# tempo_counter.net
KiCad netlist of a schematic drawn in EAGLE
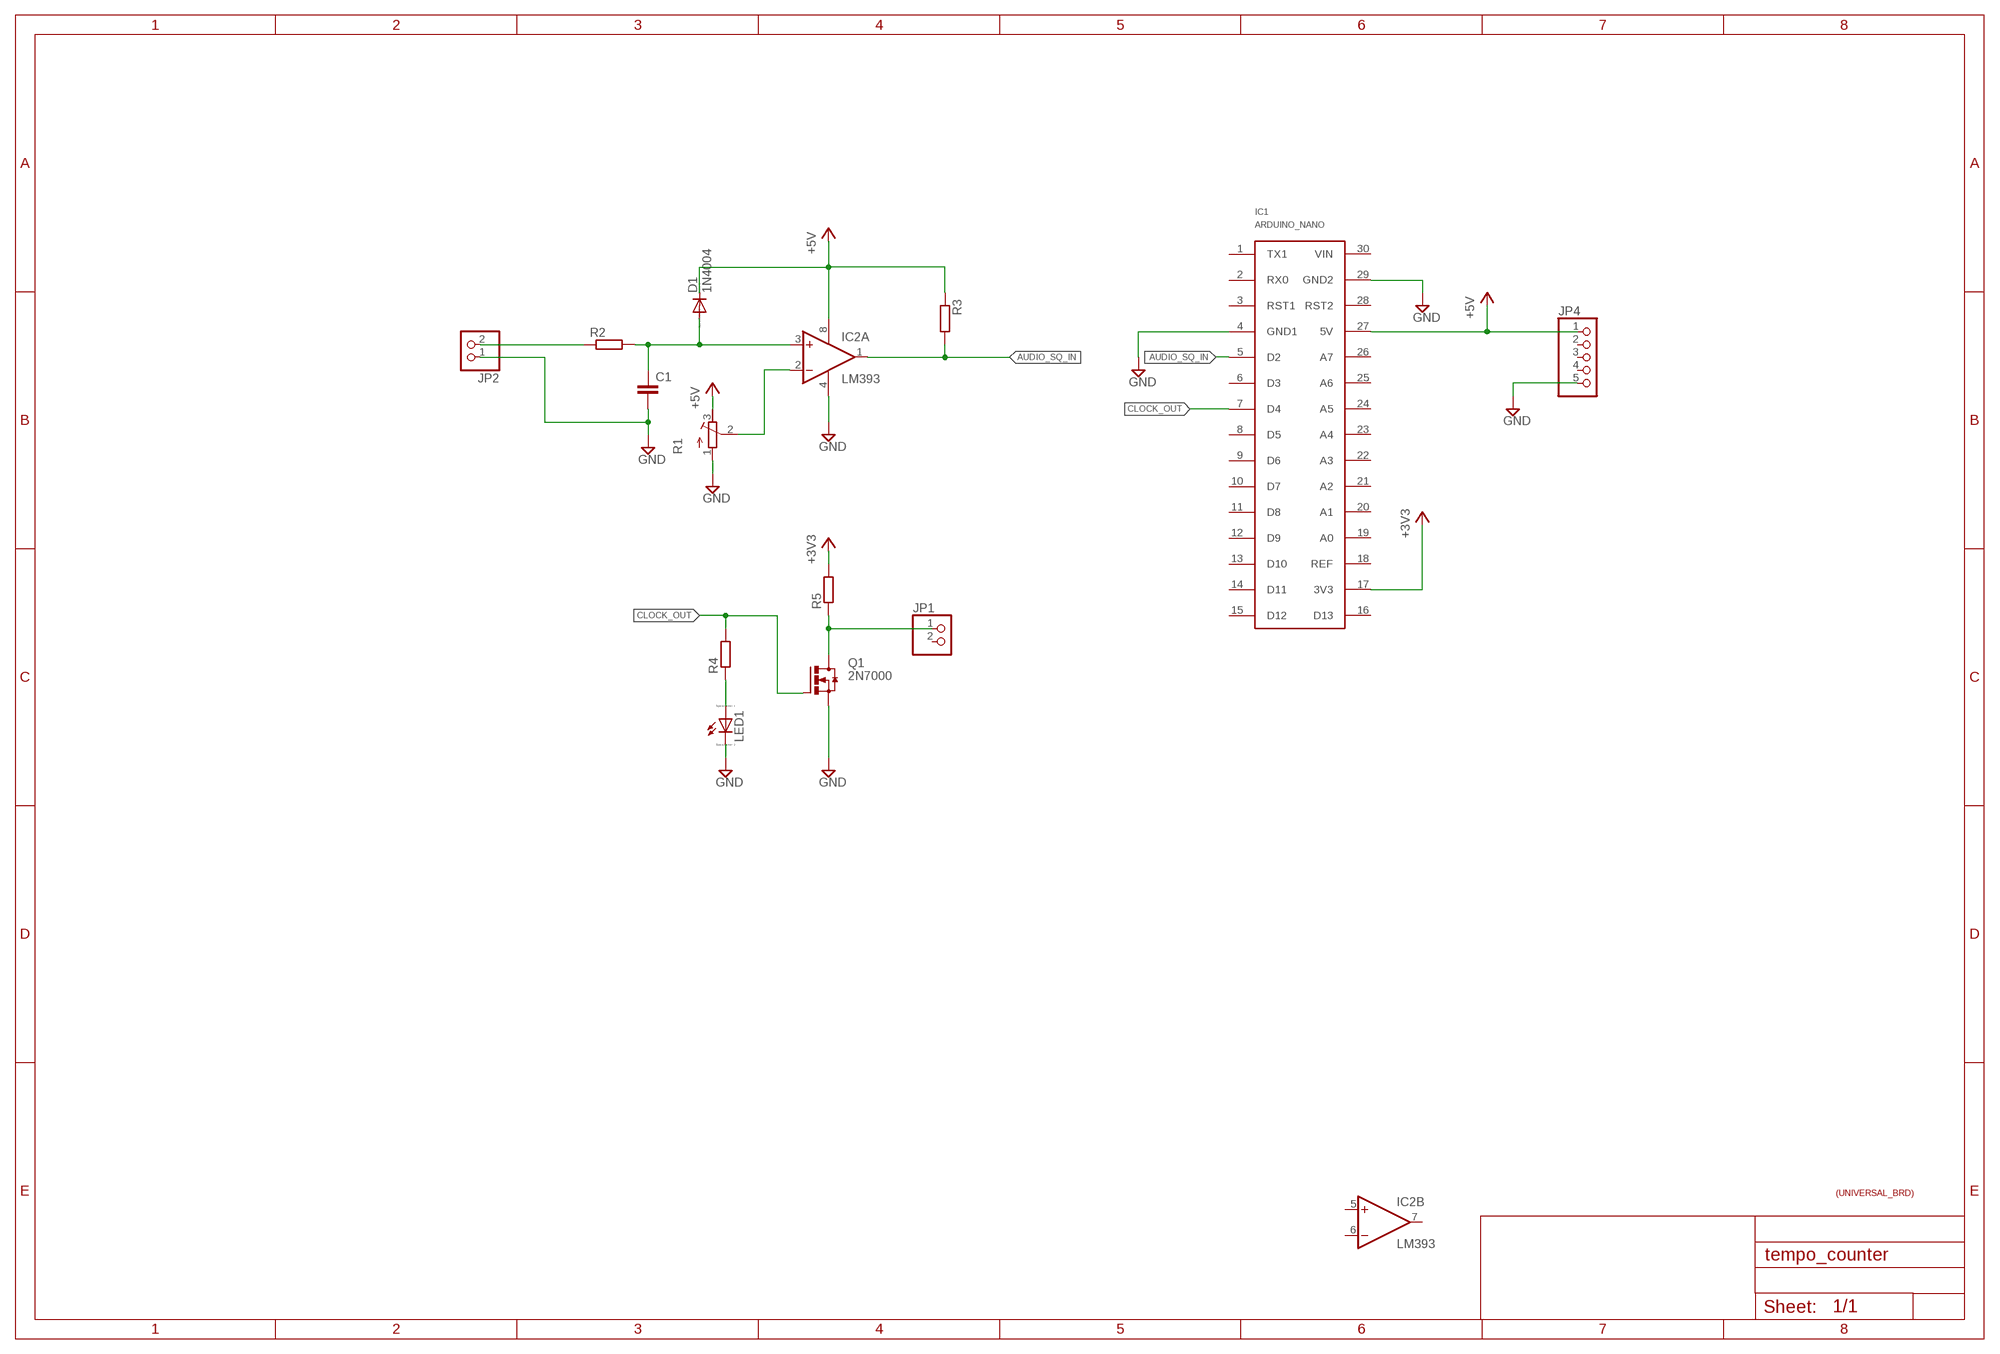
[diagram p0: schematic, sheet 1]

(export (version "E")
  (design (tool "Eeschema 10.0.6"))
  (components
    (comp (ref "C1")
      (value "C_DIP_2.54_1")
      (footprint "eagle-import:C_DIP2.54_1")
      (libsource (lib "eagle-import") (part "C_DIP_2.54_1"))
    )
    (comp (ref "D1")
      (value "1N4004")
      (footprint "eagle-import:DO41-10")
      (libsource (lib "eagle-import") (part "1N4004"))
    )
    (comp (ref "IC1")
      (value "ARDUINO_NANO")
      (footprint "eagle-import:ARDUINO_NANO")
      (libsource (lib "eagle-import") (part "ARDUINO_NANO"))
    )
    (comp (ref "IC2")
      (value "LM393")
      (footprint "eagle-import:DIL08_UNIV")
      (libsource (lib "eagle-import") (part "LM393"))
    )
    (comp (ref "JP1")
      (value "PINHD-1X2")
      (footprint "eagle-import:1X02")
      (libsource (lib "eagle-import") (part "PINHD-1X2"))
    )
    (comp (ref "JP2")
      (value "PINHD-1X2")
      (footprint "eagle-import:1X02")
      (libsource (lib "eagle-import") (part "PINHD-1X2"))
    )
    (comp (ref "JP4")
      (value "PINHD-1X5")
      (footprint "eagle-import:1X05")
      (libsource (lib "eagle-import") (part "PINHD-1X5"))
    )
    (comp (ref "LED1")
      (value "LED_ELD260")
      (footprint "eagle-import:LED_LD260")
      (libsource (lib "eagle-import") (part "LED_ELD260"))
    )
    (comp (ref "Q1")
      (value "2N7000")
      (footprint "eagle-import:TO92")
      (libsource (lib "eagle-import") (part "2N7000"))
    )
    (comp (ref "R1")
      (value "R-TRIMM64W")
      (footprint "eagle-import:RTRIM64W")
      (libsource (lib "eagle-import") (part "R-TRIMM64W"))
    )
    (comp (ref "R2")
      (value "R_DIP_4")
      (footprint "eagle-import:R_DIP2.54_4")
      (libsource (lib "eagle-import") (part "R_DIP_4"))
    )
    (comp (ref "R3")
      (value "R_DIP_4")
      (footprint "eagle-import:R_DIP2.54_4")
      (libsource (lib "eagle-import") (part "R_DIP_4"))
    )
    (comp (ref "R4")
      (value "R_DIP_4")
      (footprint "eagle-import:R_DIP2.54_4")
      (libsource (lib "eagle-import") (part "R_DIP_4"))
    )
    (comp (ref "R5")
      (value "R_DIP_4")
      (footprint "eagle-import:R_DIP2.54_4")
      (libsource (lib "eagle-import") (part "R_DIP_4"))
    )
    (comp (ref "U$1")
      (value "UNIVERSAL_BRD_72MM_47MM")
      (footprint "eagle-import:UNIVERSAL_BRD_72MM_47MM_SMALL")
      (libsource (lib "eagle-import") (part "UNIVERSAL_BRD_72MM_47MM"))
    )
  )
  (nets
    (net (code "1") (name "+3V3") (class "Default")
      (node (ref "IC1") (pin "17") (pinfunction "3V3_17") (pintype "bidirectional"))
      (node (ref "R5") (pin "2") (pinfunction "2_2") (pintype "passive"))
    )
    (net (code "2") (name "+5V") (class "Default")
      (node (ref "D1") (pin "C") (pinfunction "C_C") (pintype "passive"))
      (node (ref "IC1") (pin "27") (pinfunction "5V_27") (pintype "bidirectional"))
      (node (ref "IC2") (pin "8") (pinfunction "V+_8") (pintype "power_in"))
      (node (ref "JP4") (pin "1") (pinfunction "1_1") (pintype "passive"))
      (node (ref "R1") (pin "3") (pinfunction "E_3") (pintype "passive"))
      (node (ref "R3") (pin "1") (pinfunction "1_1") (pintype "passive"))
    )
    (net (code "3") (name "AUDIO_SQ_IN") (class "Default")
      (node (ref "IC1") (pin "5") (pinfunction "D2_5") (pintype "bidirectional"))
      (node (ref "IC2") (pin "1") (pinfunction "OUT_1") (pintype "output"))
      (node (ref "R3") (pin "2") (pinfunction "2_2") (pintype "passive"))
    )
    (net (code "4") (name "CLOCK_OUT") (class "Default")
      (node (ref "IC1") (pin "7") (pinfunction "D4_7") (pintype "bidirectional"))
      (node (ref "Q1") (pin "G") (pinfunction "G_G") (pintype "passive"))
      (node (ref "R4") (pin "2") (pinfunction "2_2") (pintype "passive"))
    )
    (net (code "5") (name "GND") (class "Default")
      (node (ref "C1") (pin "2") (pinfunction "2_2") (pintype "passive"))
      (node (ref "IC1") (pin "29") (pinfunction "GND2_29") (pintype "bidirectional"))
      (node (ref "IC1") (pin "4") (pinfunction "GND1_4") (pintype "bidirectional"))
      (node (ref "IC2") (pin "4") (pinfunction "V-_4") (pintype "power_in"))
      (node (ref "JP2") (pin "1") (pinfunction "1_1") (pintype "passive"))
      (node (ref "JP4") (pin "5") (pinfunction "5_5") (pintype "passive"))
      (node (ref "LED1") (pin "K") (pinfunction "C_K") (pintype "passive"))
      (node (ref "Q1") (pin "S") (pinfunction "S_S") (pintype "passive"))
      (node (ref "R1") (pin "1") (pinfunction "A_1") (pintype "passive"))
    )
    (net (code "6") (name "Net-(IC2A-+IN)") (class "Default")
      (node (ref "C1") (pin "1") (pinfunction "1_1") (pintype "passive"))
      (node (ref "D1") (pin "A") (pinfunction "A_A") (pintype "passive"))
      (node (ref "IC2") (pin "3") (pinfunction "+IN_3") (pintype "input"))
      (node (ref "R2") (pin "2") (pinfunction "2_2") (pintype "passive"))
    )
    (net (code "7") (name "Net-(IC2A--IN)") (class "Default")
      (node (ref "IC2") (pin "2") (pinfunction "-IN_2") (pintype "input"))
      (node (ref "R1") (pin "2") (pinfunction "S_2") (pintype "passive"))
    )
    (net (code "8") (name "Net-(JP1-Pad1)") (class "Default")
      (node (ref "JP1") (pin "1") (pinfunction "1_1") (pintype "passive"))
      (node (ref "Q1") (pin "D") (pinfunction "D_D") (pintype "passive"))
      (node (ref "R5") (pin "1") (pinfunction "1_1") (pintype "passive"))
    )
    (net (code "9") (name "Net-(JP2-Pad2)") (class "Default")
      (node (ref "JP2") (pin "2") (pinfunction "2_2") (pintype "passive"))
      (node (ref "R2") (pin "1") (pinfunction "1_1") (pintype "passive"))
    )
    (net (code "10") (name "Net-(LED1-PadA)") (class "Default")
      (node (ref "LED1") (pin "A") (pinfunction "A_A") (pintype "passive"))
      (node (ref "R4") (pin "1") (pinfunction "1_1") (pintype "passive"))
    )
    (net (code "11") (name "unconnected-(IC1-A0-Pad19)") (class "Default")
      (node (ref "IC1") (pin "19") (pinfunction "A0_19") (pintype "bidirectional"))
    )
    (net (code "12") (name "unconnected-(IC1-A1-Pad20)") (class "Default")
      (node (ref "IC1") (pin "20") (pinfunction "A1_20") (pintype "bidirectional"))
    )
    (net (code "13") (name "unconnected-(IC1-A2-Pad21)") (class "Default")
      (node (ref "IC1") (pin "21") (pinfunction "A2_21") (pintype "bidirectional"))
    )
    (net (code "14") (name "unconnected-(IC1-A3-Pad22)") (class "Default")
      (node (ref "IC1") (pin "22") (pinfunction "A3_22") (pintype "bidirectional"))
    )
    (net (code "15") (name "unconnected-(IC1-A4-Pad23)") (class "Default")
      (node (ref "IC1") (pin "23") (pinfunction "A4_23") (pintype "bidirectional"))
    )
    (net (code "16") (name "unconnected-(IC1-A5-Pad24)") (class "Default")
      (node (ref "IC1") (pin "24") (pinfunction "A5_24") (pintype "bidirectional"))
    )
    (net (code "17") (name "unconnected-(IC1-A6-Pad25)") (class "Default")
      (node (ref "IC1") (pin "25") (pinfunction "A6_25") (pintype "bidirectional"))
    )
    (net (code "18") (name "unconnected-(IC1-A7-Pad26)") (class "Default")
      (node (ref "IC1") (pin "26") (pinfunction "A7_26") (pintype "bidirectional"))
    )
    (net (code "19") (name "unconnected-(IC1-D3-Pad6)") (class "Default")
      (node (ref "IC1") (pin "6") (pinfunction "D3_6") (pintype "bidirectional"))
    )
    (net (code "20") (name "unconnected-(IC1-D5-Pad8)") (class "Default")
      (node (ref "IC1") (pin "8") (pinfunction "D5_8") (pintype "bidirectional"))
    )
    (net (code "21") (name "unconnected-(IC1-D6-Pad9)") (class "Default")
      (node (ref "IC1") (pin "9") (pinfunction "D6_9") (pintype "bidirectional"))
    )
    (net (code "22") (name "unconnected-(IC1-D7-Pad10)") (class "Default")
      (node (ref "IC1") (pin "10") (pinfunction "D7_10") (pintype "bidirectional"))
    )
    (net (code "23") (name "unconnected-(IC1-D8-Pad11)") (class "Default")
      (node (ref "IC1") (pin "11") (pinfunction "D8_11") (pintype "bidirectional"))
    )
    (net (code "24") (name "unconnected-(IC1-D9-Pad12)") (class "Default")
      (node (ref "IC1") (pin "12") (pinfunction "D9_12") (pintype "bidirectional"))
    )
    (net (code "25") (name "unconnected-(IC1-D10-Pad13)") (class "Default")
      (node (ref "IC1") (pin "13") (pinfunction "D10_13") (pintype "bidirectional"))
    )
    (net (code "26") (name "unconnected-(IC1-D11-Pad14)") (class "Default")
      (node (ref "IC1") (pin "14") (pinfunction "D11_14") (pintype "bidirectional"))
    )
    (net (code "27") (name "unconnected-(IC1-D12-Pad15)") (class "Default")
      (node (ref "IC1") (pin "15") (pinfunction "D12_15") (pintype "bidirectional"))
    )
    (net (code "28") (name "unconnected-(IC1-D13-Pad16)") (class "Default")
      (node (ref "IC1") (pin "16") (pinfunction "D13_16") (pintype "bidirectional"))
    )
    (net (code "29") (name "unconnected-(IC1-REF-Pad18)") (class "Default")
      (node (ref "IC1") (pin "18") (pinfunction "REF_18") (pintype "bidirectional"))
    )
    (net (code "30") (name "unconnected-(IC1-RST1-Pad3)") (class "Default")
      (node (ref "IC1") (pin "3") (pinfunction "RST1_3") (pintype "bidirectional"))
    )
    (net (code "31") (name "unconnected-(IC1-RST2-Pad28)") (class "Default")
      (node (ref "IC1") (pin "28") (pinfunction "RST2_28") (pintype "bidirectional"))
    )
    (net (code "32") (name "unconnected-(IC1-RX0-Pad2)") (class "Default")
      (node (ref "IC1") (pin "2") (pinfunction "RX0_2") (pintype "bidirectional"))
    )
    (net (code "33") (name "unconnected-(IC1-TX1-Pad1)") (class "Default")
      (node (ref "IC1") (pin "1") (pinfunction "TX1_1") (pintype "bidirectional"))
    )
    (net (code "34") (name "unconnected-(IC1-VIN-Pad30)") (class "Default")
      (node (ref "IC1") (pin "30") (pinfunction "VIN_30") (pintype "bidirectional"))
    )
    (net (code "35") (name "unconnected-(IC2B-+IN-Pad5)") (class "Default")
      (node (ref "IC2") (pin "5") (pinfunction "+IN_5") (pintype "input"))
    )
    (net (code "36") (name "unconnected-(IC2B--IN-Pad6)") (class "Default")
      (node (ref "IC2") (pin "6") (pinfunction "-IN_6") (pintype "input"))
    )
    (net (code "37") (name "unconnected-(IC2B-OUT-Pad7)") (class "Default")
      (node (ref "IC2") (pin "7") (pinfunction "OUT_7") (pintype "output"))
    )
    (net (code "38") (name "unconnected-(JP1-Pad2)") (class "Default")
      (node (ref "JP1") (pin "2") (pinfunction "2_2") (pintype "passive"))
    )
    (net (code "39") (name "unconnected-(JP4-Pad2)") (class "Default")
      (node (ref "JP4") (pin "2") (pinfunction "2_2") (pintype "passive"))
    )
    (net (code "40") (name "unconnected-(JP4-Pad3)") (class "Default")
      (node (ref "JP4") (pin "3") (pinfunction "3_3") (pintype "passive"))
    )
    (net (code "41") (name "unconnected-(JP4-Pad4)") (class "Default")
      (node (ref "JP4") (pin "4") (pinfunction "4_4") (pintype "passive"))
    )
  )
)
